# design.net
KiCad netlist of a schematic drawn in Altium Designer
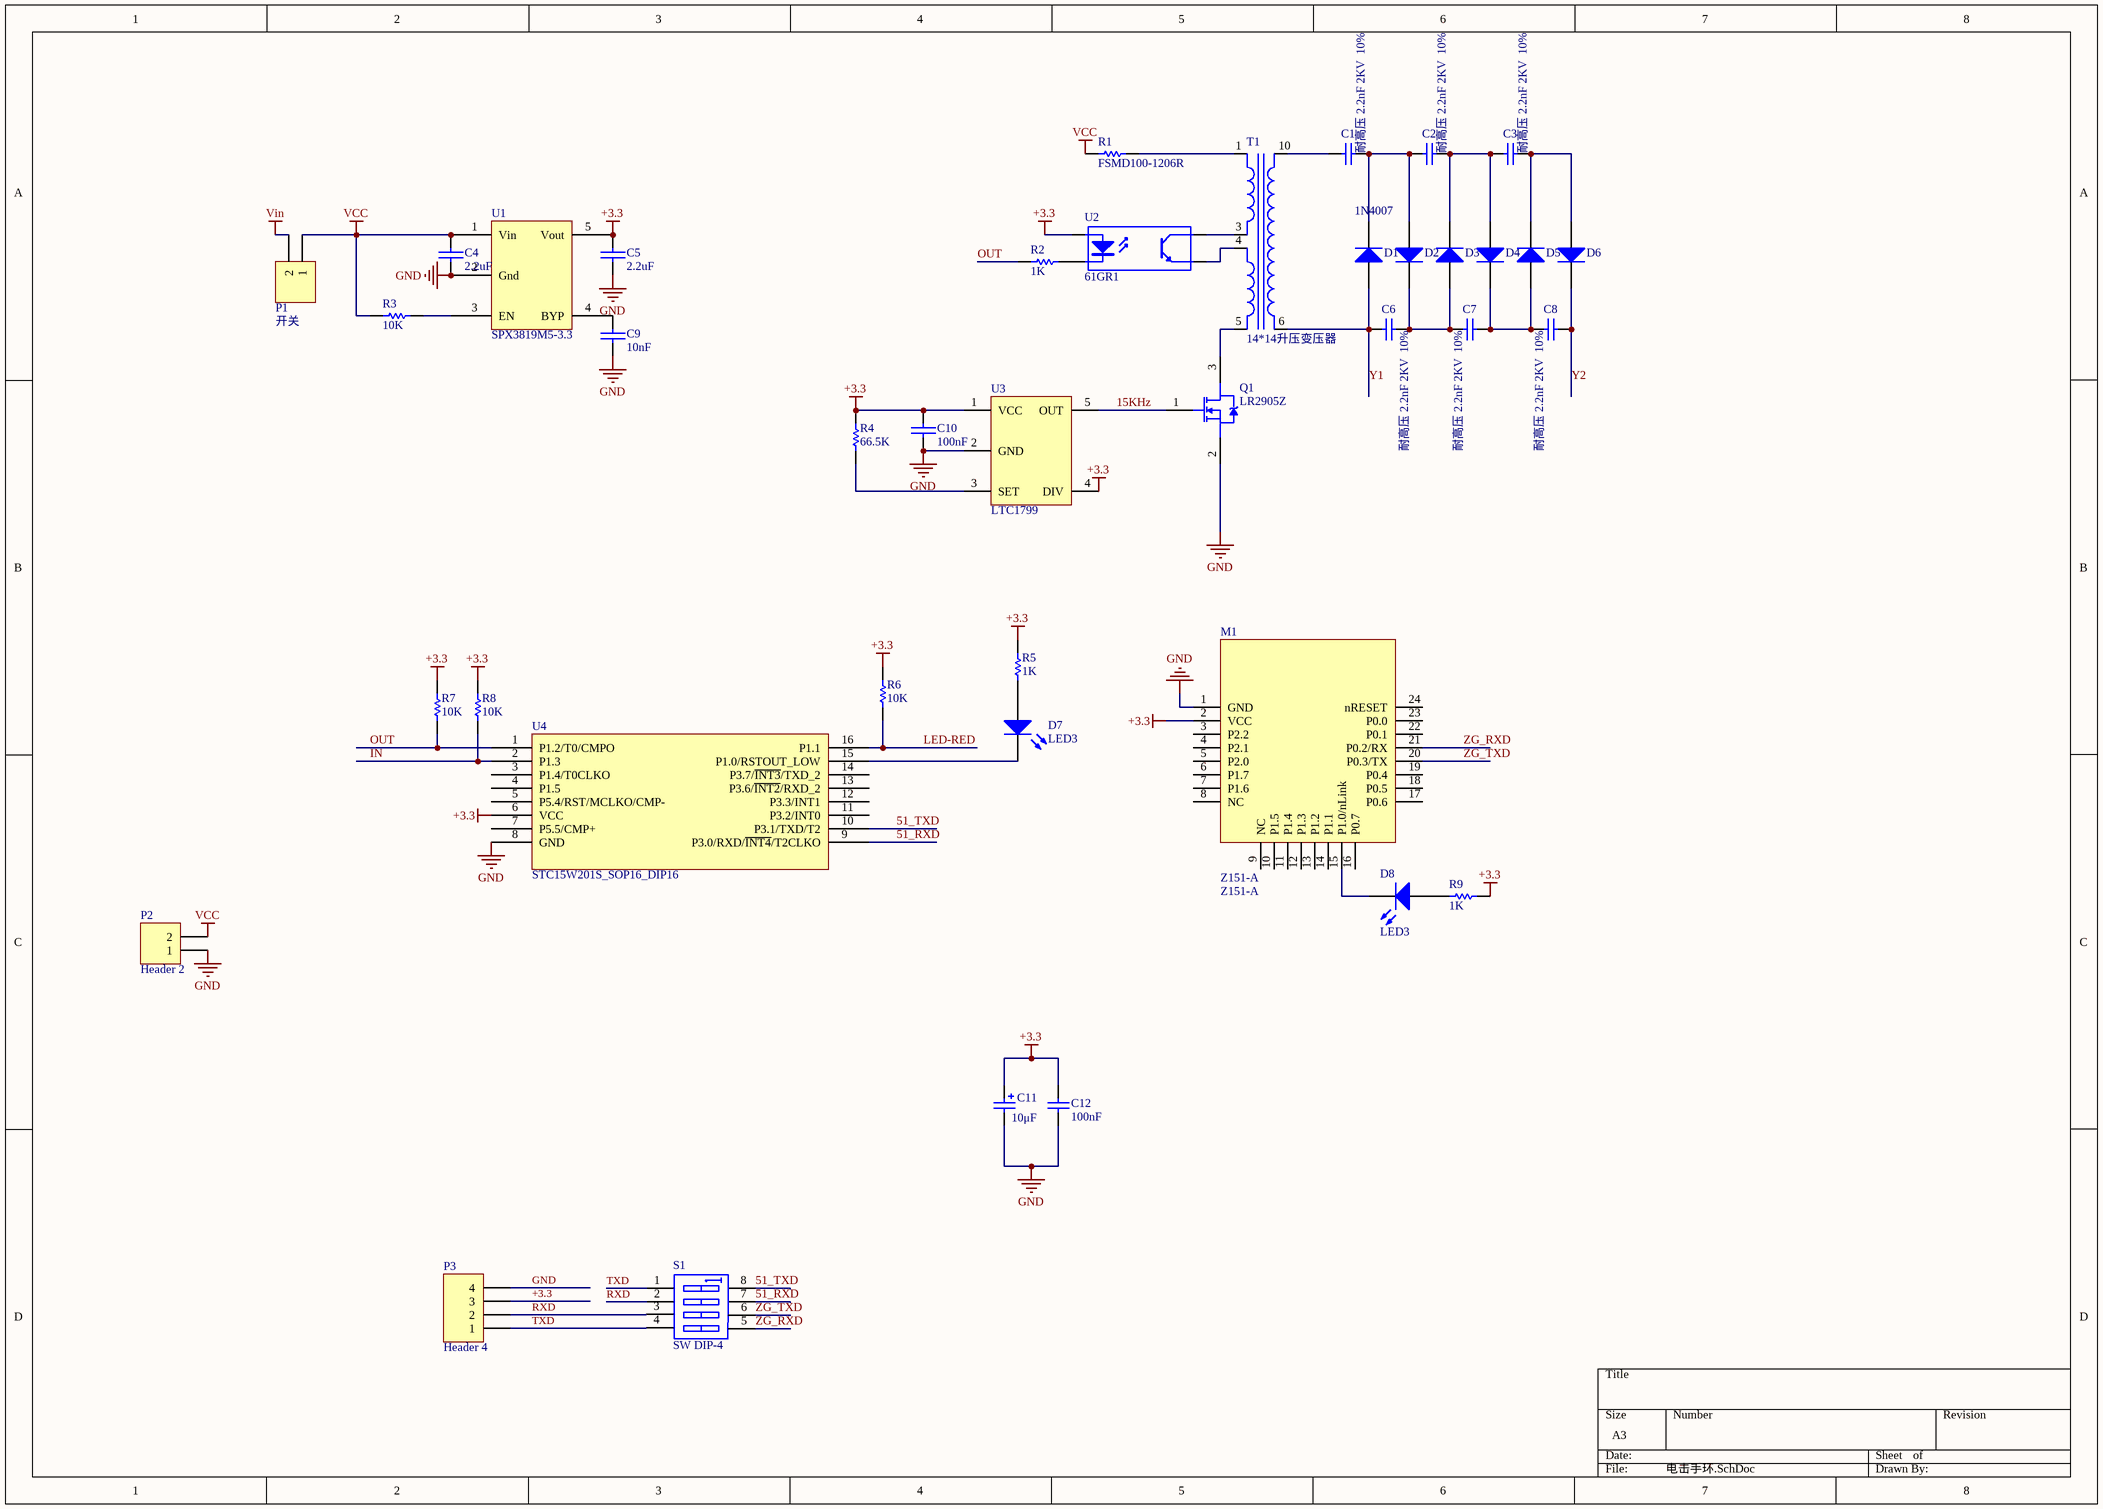
[diagram p0: 电击手环.SchDoc]

(export (version "E")
  (design (tool "Eeschema 10.0.6"))
  (components
    (comp (ref "C1")
      (value "耐高压 2.2nF 2KV  10%")
      (footprint "1206")
      (description "Capacitor")
      (fields (field (name "PUBLISHER") "Altium Limited"))
      (libsource (lib "AA-SCH") (part "Cap"))
    )
    (comp (ref "C2")
      (value "耐高压 2.2nF 2KV  10%")
      (footprint "1206")
      (description "Capacitor")
      (fields (field (name "PUBLISHER") "Altium Limited"))
      (libsource (lib "AA-SCH") (part "Cap"))
    )
    (comp (ref "C3")
      (value "耐高压 2.2nF 2KV  10%")
      (footprint "1206")
      (description "Capacitor")
      (fields (field (name "PUBLISHER") "Altium Limited"))
      (libsource (lib "AA-SCH") (part "Cap"))
    )
    (comp (ref "C4")
      (value "2.2uF")
      (footprint "0603")
      (description "Capacitor")
      (libsource (lib "*") (part "CAP"))
    )
    (comp (ref "C5")
      (value "2.2uF")
      (footprint "0603")
      (description "Capacitor")
      (libsource (lib "*") (part "CAP"))
    )
    (comp (ref "C6")
      (value "耐高压 2.2nF 2KV  10%")
      (footprint "1206")
      (description "Capacitor")
      (fields (field (name "PUBLISHER") "Altium Limited"))
      (libsource (lib "AA-SCH") (part "Cap"))
    )
    (comp (ref "C7")
      (value "耐高压 2.2nF 2KV  10%")
      (footprint "1206")
      (description "Capacitor")
      (fields (field (name "PUBLISHER") "Altium Limited"))
      (libsource (lib "AA-SCH") (part "Cap"))
    )
    (comp (ref "C8")
      (value "耐高压 2.2nF 2KV  10%")
      (footprint "1206")
      (description "Capacitor")
      (fields (field (name "PUBLISHER") "Altium Limited"))
      (libsource (lib "AA-SCH") (part "Cap"))
    )
    (comp (ref "C9")
      (value "10nF")
      (footprint "0603")
      (description "Capacitor")
      (libsource (lib "*") (part "CAP"))
    )
    (comp (ref "C10")
      (value "100nF")
      (footprint "R0603(1608)")
      (description "Capacitor")
      (libsource (lib "") (part "CAP_1"))
    )
    (comp (ref "C11")
      (value "10μF")
      (footprint "0603")
      (description "Polarized Capacitor (Radial)")
      (fields
        (field (name "MANUFACTURER") "Generic Components")
        (field (name "PUBLISHER") "Altium Hobart Technology Centre")
      )
      (libsource (lib "Miscellaneous Devices") (part "Cap Pol1"))
    )
    (comp (ref "C12")
      (value "100nF")
      (footprint "0603")
      (description "Capacitor")
      (fields (field (name "PUBLISHER") "Altium Limited"))
      (libsource (lib "Miscellaneous Devices") (part "Cap"))
    )
    (comp (ref "D1")
      (value "1N4007")
      (footprint "DO-214AA")
      (description "二极管")
      (fields (field (name "PUBLISHER") "Altium Limited"))
      (libsource (lib "AA-SCH") (part "Diode_1"))
    )
    (comp (ref "D2")
      (value "1N4007")
      (footprint "DO-214AA")
      (description "二极管")
      (fields (field (name "PUBLISHER") "Altium Limited"))
      (libsource (lib "AA-SCH") (part "Diode_1"))
    )
    (comp (ref "D3")
      (value "1N4007")
      (footprint "DO-214AA")
      (description "二极管")
      (fields (field (name "PUBLISHER") "Altium Limited"))
      (libsource (lib "AA-SCH") (part "Diode_1"))
    )
    (comp (ref "D4")
      (value "1N4007")
      (footprint "DO-214AA")
      (description "二极管")
      (fields (field (name "PUBLISHER") "Altium Limited"))
      (libsource (lib "AA-SCH") (part "Diode_1"))
    )
    (comp (ref "D5")
      (value "1N4007")
      (footprint "DO-214AA")
      (description "二极管")
      (fields (field (name "PUBLISHER") "Altium Limited"))
      (libsource (lib "AA-SCH") (part "Diode_1"))
    )
    (comp (ref "D6")
      (value "1N4007")
      (footprint "DO-214AA")
      (description "二极管")
      (fields (field (name "PUBLISHER") "Altium Limited"))
      (libsource (lib "AA-SCH") (part "Diode_1"))
    )
    (comp (ref "D7")
      (value "LED3")
      (footprint "LED0805")
      (description "Typical BLUE SiC LED")
      (fields (field (name "PUBLISHER") "Altium Limited"))
      (libsource (lib "Miscellaneous Devices") (part "LED3"))
    )
    (comp (ref "D8")
      (value "LED3")
      (footprint "LED0805")
      (description "Typical BLUE SiC LED")
      (fields (field (name "PUBLISHER") "Altium Limited"))
      (libsource (lib "Miscellaneous Devices") (part "LED3"))
    )
    (comp (ref "M1")
      (value "Z151-A")
      (footprint "Z151-A")
      (description "Z151板载天线版本：Z151-A")
      (fields (field (name "MANUFACTURER") "Ghostyu") (field (name "PART VALUE") "Z151-A"))
      (libsource (lib "AA-SCH") (part "Z151-A"))
    )
    (comp (ref "P1")
      (value "开关")
      (footprint "HDR1X2")
      (description "Header, 2-Pin")
      (fields (field (name "PUBLISHER") "Altium Limited"))
      (libsource (lib "") (part "Header 2_1"))
    )
    (comp (ref "P2")
      (value "Header 2")
      (footprint "HDR1X2")
      (description "Header, 2-Pin")
      (fields (field (name "PUBLISHER") "Altium Limited"))
      (libsource (lib "Miscellaneous Connectors") (part "Header 2"))
    )
    (comp (ref "P3")
      (value "Header 4")
      (footprint "HDR1X4")
      (description "Header, 4-Pin")
      (fields (field (name "PUBLISHER") "Altium Limited"))
      (libsource (lib "Miscellaneous Connectors") (part "Header 4"))
    )
    (comp (ref "Q1")
      (value "LR2905Z")
      (footprint "TO-252AA_N")
      (description "N-Channel MOSFET")
      (fields (field (name "PUBLISHER") "Altium Limited"))
      (libsource (lib "AA-SCH") (part "MOSFET-N"))
    )
    (comp (ref "R1")
      (value "FSMD100-1206R")
      (footprint "1206")
      (description "Resistor")
      (fields (field (name "PUBLISHER") "Altium Limited"))
      (libsource (lib "Miscellaneous Devices") (part "Res1"))
    )
    (comp (ref "R2")
      (value "1K")
      (footprint "R0805(2012)")
      (description "Resistor")
      (fields (field (name "PUBLISHER") "Altium Limited"))
      (libsource (lib "Miscellaneous Devices") (part "Res1"))
    )
    (comp (ref "R3")
      (value "10K")
      (footprint "0603")
      (description "Resistor")
      (fields (field (name "PUBLISHER") "Altium Limited"))
      (libsource (lib "Miscellaneous Devices") (part "Res1"))
    )
    (comp (ref "R4")
      (value "66.5K")
      (footprint "R0603(1608)")
      (description "Resistor")
      (fields (field (name "PUBLISHER") "Altium Limited"))
      (libsource (lib "Miscellaneous Devices") (part "Res1"))
    )
    (comp (ref "R5")
      (value "1K")
      (footprint "0603")
      (description "Resistor")
      (fields (field (name "PUBLISHER") "Altium Limited"))
      (libsource (lib "Miscellaneous Devices") (part "Res1"))
    )
    (comp (ref "R6")
      (value "10K")
      (footprint "0603")
      (description "Resistor")
      (fields (field (name "PUBLISHER") "Altium Limited"))
      (libsource (lib "Miscellaneous Devices") (part "Res1"))
    )
    (comp (ref "R7")
      (value "10K")
      (footprint "0603")
      (description "Resistor")
      (fields (field (name "PUBLISHER") "Altium Limited"))
      (libsource (lib "Miscellaneous Devices") (part "Res1"))
    )
    (comp (ref "R8")
      (value "10K")
      (footprint "0603")
      (description "Resistor")
      (fields (field (name "PUBLISHER") "Altium Limited"))
      (libsource (lib "Miscellaneous Devices") (part "Res1"))
    )
    (comp (ref "R9")
      (value "1K")
      (footprint "0603")
      (description "Resistor")
      (fields (field (name "PUBLISHER") "Altium Limited"))
      (libsource (lib "Miscellaneous Devices") (part "Res1"))
    )
    (comp (ref "S1")
      (value "SW DIP-4")
      (footprint "拨码开关1.27-5.4-4P")
      (description "DIP Switch, 2 Position, SPST")
      (fields (field (name "PUBLISHER") "Altium Limited"))
      (libsource (lib "yuanjian ") (part "SW DIP-4"))
    )
    (comp (ref "T1")
      (value "14*14升压变压器")
      (footprint "14*14 升压变压器")
      (libsource (lib "AA-SCH") (part "14*14升压变压器"))
    )
    (comp (ref "U1")
      (value "SPX3819M5-3.3")
      (footprint "AA-PCB :SOT-25")
      (description "Low Noise, 300mA and 500mA CMOS LDO Regulators")
      (libsource (lib "AA-SCH") (part "SP6205"))
    )
    (comp (ref "U2")
      (value "61GR1")
      (footprint "G3VM")
      (description "4-Pin Phototransistor Optocoupler")
      (fields (field (name "PUBLISHER") "Altium Limited"))
      (libsource (lib "Miscellaneous Devices") (part "Optoisolator1"))
    )
    (comp (ref "U3") (value "LTC1799") (footprint "SOT-25B") (libsource (lib "AA-SCH") (part "LTC1799")))
    (comp (ref "U4")
      (value "STC15W201S_SOP16_DIP16")
      (footprint "SO-16")
      (libsource (lib "AA-SCH") (part "STC15W201S_SOP16_DIP16"))
    )
  )
  (nets
    (net (code "1") (name "+3.3") (class "Default")
      (node (ref "C10") (pin "1") (pinfunction "1_1") (pintype "passive"))
      (node (ref "C11") (pin "1") (pinfunction "1_1") (pintype "passive"))
      (node (ref "C12") (pin "2") (pinfunction "2_2") (pintype "passive"))
      (node (ref "C5") (pin "1") (pinfunction "1_1") (pintype "passive"))
      (node (ref "M1") (pin "2") (pinfunction "VCC_2") (pintype "passive"))
      (node (ref "P3") (pin "3") (pinfunction "3_3") (pintype "passive"))
      (node (ref "R4") (pin "1") (pinfunction "1_1") (pintype "passive"))
      (node (ref "R5") (pin "1") (pinfunction "1_1") (pintype "passive"))
      (node (ref "R6") (pin "2") (pinfunction "2_2") (pintype "passive"))
      (node (ref "R7") (pin "2") (pinfunction "2_2") (pintype "passive"))
      (node (ref "R8") (pin "2") (pinfunction "2_2") (pintype "passive"))
      (node (ref "R9") (pin "1") (pinfunction "1_1") (pintype "passive"))
      (node (ref "U1") (pin "5") (pinfunction "Vout_5") (pintype "power_in"))
      (node (ref "U2") (pin "1") (pinfunction "A_1") (pintype "passive"))
      (node (ref "U3") (pin "1") (pinfunction "VCC_1") (pintype "passive"))
      (node (ref "U3") (pin "4") (pinfunction "DIV_4") (pintype "passive"))
      (node (ref "U4") (pin "6") (pinfunction "VCC_6") (pintype "passive"))
    )
    (net (code "2") (name "/15KHz") (class "Default")
      (node (ref "Q1") (pin "1") (pinfunction "G1_1") (pintype "power_in"))
      (node (ref "U3") (pin "5") (pinfunction "OUT_5") (pintype "passive"))
    )
    (net (code "3") (name "/51_RXD") (class "Default")
      (node (ref "S1") (pin "7") (pinfunction "7_7") (pintype "passive"))
      (node (ref "U4") (pin "9") (pinfunction "P3.0/RXD/~{INT4}/T2CLKO_9") (pintype "passive"))
    )
    (net (code "4") (name "/51_TXD") (class "Default")
      (node (ref "S1") (pin "8") (pinfunction "8_8") (pintype "passive"))
      (node (ref "U4") (pin "10") (pinfunction "P3.1/TXD/T2_10") (pintype "passive"))
    )
    (net (code "5") (name "/IN") (class "Default")
      (node (ref "R8") (pin "1") (pinfunction "1_1") (pintype "passive"))
      (node (ref "U4") (pin "2") (pinfunction "P1.3_2") (pintype "passive"))
    )
    (net (code "6") (name "/LED-RED") (class "Default")
      (node (ref "R6") (pin "1") (pinfunction "1_1") (pintype "passive"))
      (node (ref "U4") (pin "16") (pinfunction "P1.1_16") (pintype "passive"))
    )
    (net (code "7") (name "/OUT") (class "Default")
      (node (ref "R2") (pin "2") (pinfunction "2_2") (pintype "passive"))
      (node (ref "R7") (pin "1") (pinfunction "1_1") (pintype "passive"))
      (node (ref "U4") (pin "1") (pinfunction "P1.2/T0/CMPO_1") (pintype "passive"))
    )
    (net (code "8") (name "/RXD") (class "Default")
      (node (ref "P3") (pin "2") (pinfunction "2_2") (pintype "passive"))
      (node (ref "S1") (pin "2") (pinfunction "2_2") (pintype "passive"))
      (node (ref "S1") (pin "3") (pinfunction "3_3") (pintype "passive"))
    )
    (net (code "9") (name "/TXD") (class "Default")
      (node (ref "P3") (pin "1") (pinfunction "1_1") (pintype "passive"))
      (node (ref "S1") (pin "1") (pinfunction "1_1") (pintype "passive"))
      (node (ref "S1") (pin "4") (pinfunction "4_4") (pintype "passive"))
    )
    (net (code "10") (name "/Y1") (class "Default")
      (node (ref "C6") (pin "2") (pinfunction "2_2") (pintype "passive"))
      (node (ref "D1") (pin "1") (pinfunction "A_1") (pintype "passive"))
      (node (ref "T1") (pin "6") (pinfunction "Pri+_6") (pintype "passive"))
    )
    (net (code "11") (name "/Y2") (class "Default")
      (node (ref "C8") (pin "1") (pinfunction "1_1") (pintype "passive"))
      (node (ref "D6") (pin "2") (pinfunction "K_2") (pintype "passive"))
    )
    (net (code "12") (name "/ZG_RXD") (class "Default")
      (node (ref "M1") (pin "21") (pinfunction "P0.2/RX_21") (pintype "passive"))
      (node (ref "S1") (pin "5") (pinfunction "5_5") (pintype "passive"))
    )
    (net (code "13") (name "/ZG_TXD") (class "Default")
      (node (ref "M1") (pin "20") (pinfunction "P0.3/TX_20") (pintype "passive"))
      (node (ref "S1") (pin "6") (pinfunction "6_6") (pintype "passive"))
    )
    (net (code "14") (name "GND") (class "Default")
      (node (ref "C10") (pin "2") (pinfunction "2_2") (pintype "passive"))
      (node (ref "C11") (pin "2") (pinfunction "2_2") (pintype "passive"))
      (node (ref "C12") (pin "1") (pinfunction "1_1") (pintype "passive"))
      (node (ref "C4") (pin "2") (pinfunction "2_2") (pintype "passive"))
      (node (ref "C5") (pin "2") (pinfunction "2_2") (pintype "passive"))
      (node (ref "C9") (pin "2") (pinfunction "2_2") (pintype "passive"))
      (node (ref "M1") (pin "1") (pinfunction "GND_1") (pintype "passive"))
      (node (ref "P2") (pin "1") (pinfunction "1_1") (pintype "passive"))
      (node (ref "P3") (pin "4") (pinfunction "4_4") (pintype "passive"))
      (node (ref "Q1") (pin "2") (pinfunction "S1_2") (pintype "power_in"))
      (node (ref "U1") (pin "2") (pinfunction "Gnd_2") (pintype "power_in"))
      (node (ref "U3") (pin "2") (pinfunction "GND_2") (pintype "passive"))
      (node (ref "U4") (pin "8") (pinfunction "GND_8") (pintype "passive"))
    )
    (net (code "15") (name "Net-(D1-K)") (class "Default")
      (node (ref "C1") (pin "1") (pinfunction "1_1") (pintype "passive"))
      (node (ref "C2") (pin "2") (pinfunction "2_2") (pintype "passive"))
      (node (ref "D1") (pin "2") (pinfunction "K_2") (pintype "passive"))
      (node (ref "D2") (pin "1") (pinfunction "A_1") (pintype "passive"))
    )
    (net (code "16") (name "Net-(D2-K)") (class "Default")
      (node (ref "C6") (pin "1") (pinfunction "1_1") (pintype "passive"))
      (node (ref "C7") (pin "2") (pinfunction "2_2") (pintype "passive"))
      (node (ref "D2") (pin "2") (pinfunction "K_2") (pintype "passive"))
      (node (ref "D3") (pin "1") (pinfunction "A_1") (pintype "passive"))
    )
    (net (code "17") (name "Net-(D3-K)") (class "Default")
      (node (ref "C2") (pin "1") (pinfunction "1_1") (pintype "passive"))
      (node (ref "C3") (pin "2") (pinfunction "2_2") (pintype "passive"))
      (node (ref "D3") (pin "2") (pinfunction "K_2") (pintype "passive"))
      (node (ref "D4") (pin "1") (pinfunction "A_1") (pintype "passive"))
    )
    (net (code "18") (name "Net-(D4-K)") (class "Default")
      (node (ref "C7") (pin "1") (pinfunction "1_1") (pintype "passive"))
      (node (ref "C8") (pin "2") (pinfunction "2_2") (pintype "passive"))
      (node (ref "D4") (pin "2") (pinfunction "K_2") (pintype "passive"))
      (node (ref "D5") (pin "1") (pinfunction "A_1") (pintype "passive"))
    )
    (net (code "19") (name "Net-(D5-K)") (class "Default")
      (node (ref "C3") (pin "1") (pinfunction "1_1") (pintype "passive"))
      (node (ref "D5") (pin "2") (pinfunction "K_2") (pintype "passive"))
      (node (ref "D6") (pin "1") (pinfunction "A_1") (pintype "passive"))
    )
    (net (code "20") (name "Net-(D7-A)") (class "Default")
      (node (ref "D7") (pin "1") (pinfunction "A_1") (pintype "passive"))
      (node (ref "R5") (pin "2") (pinfunction "2_2") (pintype "passive"))
    )
    (net (code "21") (name "Net-(D7-K)") (class "Default")
      (node (ref "D7") (pin "2") (pinfunction "K_2") (pintype "passive"))
      (node (ref "U4") (pin "15") (pinfunction "P1.0/RSTOUT_LOW_15") (pintype "passive"))
    )
    (net (code "22") (name "Net-(D8-A)") (class "Default")
      (node (ref "D8") (pin "1") (pinfunction "A_1") (pintype "passive"))
      (node (ref "R9") (pin "2") (pinfunction "2_2") (pintype "passive"))
    )
    (net (code "23") (name "Net-(D8-K)") (class "Default")
      (node (ref "D8") (pin "2") (pinfunction "K_2") (pintype "passive"))
      (node (ref "M1") (pin "15") (pinfunction "P1.0/nLink_15") (pintype "passive"))
    )
    (net (code "24") (name "Net-(Q1-D1)") (class "Default")
      (node (ref "Q1") (pin "3") (pinfunction "D1_3") (pintype "power_in"))
      (node (ref "T1") (pin "5") (pinfunction "Sec1+_5") (pintype "passive"))
    )
    (net (code "25") (name "Net-(T1-Pri-)") (class "Default")
      (node (ref "C1") (pin "2") (pinfunction "2_2") (pintype "passive"))
      (node (ref "T1") (pin "10") (pinfunction "Pri-_10") (pintype "passive"))
    )
    (net (code "26") (name "Net-(T1-Sec1-)") (class "Default")
      (node (ref "T1") (pin "4") (pinfunction "Sec1-_4") (pintype "passive"))
      (node (ref "U2") (pin "3") (pinfunction "E_3") (pintype "passive"))
    )
    (net (code "27") (name "Net-(T1-Sec2+)") (class "Default")
      (node (ref "T1") (pin "3") (pinfunction "Sec2+_3") (pintype "passive"))
      (node (ref "U2") (pin "4") (pinfunction "C_4") (pintype "passive"))
    )
    (net (code "28") (name "Net-(T1-Sec2-)") (class "Default")
      (node (ref "R1") (pin "2") (pinfunction "2_2") (pintype "passive"))
      (node (ref "T1") (pin "1") (pinfunction "Sec2-_1") (pintype "passive"))
    )
    (net (code "29") (name "Net-(U1-BYP)") (class "Default")
      (node (ref "C9") (pin "1") (pinfunction "1_1") (pintype "passive"))
      (node (ref "U1") (pin "4") (pinfunction "BYP_4") (pintype "power_in"))
    )
    (net (code "30") (name "Net-(U1-EN)") (class "Default")
      (node (ref "R3") (pin "1") (pinfunction "1_1") (pintype "passive"))
      (node (ref "U1") (pin "3") (pinfunction "EN_3") (pintype "power_in"))
    )
    (net (code "31") (name "Net-(U2-K)") (class "Default")
      (node (ref "R2") (pin "1") (pinfunction "1_1") (pintype "passive"))
      (node (ref "U2") (pin "2") (pinfunction "K_2") (pintype "passive"))
    )
    (net (code "32") (name "Net-(U3-SET)") (class "Default")
      (node (ref "R4") (pin "2") (pinfunction "2_2") (pintype "passive"))
      (node (ref "U3") (pin "3") (pinfunction "SET_3") (pintype "passive"))
    )
    (net (code "33") (name "VCC") (class "Default")
      (node (ref "C4") (pin "1") (pinfunction "1_1") (pintype "passive"))
      (node (ref "P1") (pin "1") (pinfunction "1_1") (pintype "passive"))
      (node (ref "P2") (pin "2") (pinfunction "2_2") (pintype "passive"))
      (node (ref "R1") (pin "1") (pinfunction "1_1") (pintype "passive"))
      (node (ref "R3") (pin "2") (pinfunction "2_2") (pintype "passive"))
      (node (ref "U1") (pin "1") (pinfunction "Vin_1") (pintype "power_in"))
    )
    (net (code "34") (name "Vin") (class "Default")
      (node (ref "P1") (pin "2") (pinfunction "2_2") (pintype "passive"))
    )
    (net (code "35") (name "unconnected-(M1-NC-Pad8)") (class "Default")
      (node (ref "M1") (pin "8") (pinfunction "NC_8") (pintype "passive"))
    )
    (net (code "36") (name "unconnected-(M1-NC-Pad9)") (class "Default")
      (node (ref "M1") (pin "9") (pinfunction "NC_9") (pintype "passive"))
    )
    (net (code "37") (name "unconnected-(M1-P0.0-Pad23)") (class "Default")
      (node (ref "M1") (pin "23") (pinfunction "P0.0_23") (pintype "passive"))
    )
    (net (code "38") (name "unconnected-(M1-P0.1-Pad22)") (class "Default")
      (node (ref "M1") (pin "22") (pinfunction "P0.1_22") (pintype "passive"))
    )
    (net (code "39") (name "unconnected-(M1-P0.4-Pad19)") (class "Default")
      (node (ref "M1") (pin "19") (pinfunction "P0.4_19") (pintype "passive"))
    )
    (net (code "40") (name "unconnected-(M1-P0.5-Pad18)") (class "Default")
      (node (ref "M1") (pin "18") (pinfunction "P0.5_18") (pintype "passive"))
    )
    (net (code "41") (name "unconnected-(M1-P0.6-Pad17)") (class "Default")
      (node (ref "M1") (pin "17") (pinfunction "P0.6_17") (pintype "passive"))
    )
    (net (code "42") (name "unconnected-(M1-P0.7-Pad16)") (class "Default")
      (node (ref "M1") (pin "16") (pinfunction "P0.7_16") (pintype "passive"))
    )
    (net (code "43") (name "unconnected-(M1-P1.1-Pad14)") (class "Default")
      (node (ref "M1") (pin "14") (pinfunction "P1.1_14") (pintype "passive"))
    )
    (net (code "44") (name "unconnected-(M1-P1.2-Pad13)") (class "Default")
      (node (ref "M1") (pin "13") (pinfunction "P1.2_13") (pintype "passive"))
    )
    (net (code "45") (name "unconnected-(M1-P1.3-Pad12)") (class "Default")
      (node (ref "M1") (pin "12") (pinfunction "P1.3_12") (pintype "passive"))
    )
    (net (code "46") (name "unconnected-(M1-P1.4-Pad11)") (class "Default")
      (node (ref "M1") (pin "11") (pinfunction "P1.4_11") (pintype "passive"))
    )
    (net (code "47") (name "unconnected-(M1-P1.5-Pad10)") (class "Default")
      (node (ref "M1") (pin "10") (pinfunction "P1.5_10") (pintype "passive"))
    )
    (net (code "48") (name "unconnected-(M1-P1.6-Pad7)") (class "Default")
      (node (ref "M1") (pin "7") (pinfunction "P1.6_7") (pintype "passive"))
    )
    (net (code "49") (name "unconnected-(M1-P1.7-Pad6)") (class "Default")
      (node (ref "M1") (pin "6") (pinfunction "P1.7_6") (pintype "passive"))
    )
    (net (code "50") (name "unconnected-(M1-P2.0-Pad5)") (class "Default")
      (node (ref "M1") (pin "5") (pinfunction "P2.0_5") (pintype "passive"))
    )
    (net (code "51") (name "unconnected-(M1-P2.1-Pad4)") (class "Default")
      (node (ref "M1") (pin "4") (pinfunction "P2.1_4") (pintype "passive"))
    )
    (net (code "52") (name "unconnected-(M1-P2.2-Pad3)") (class "Default")
      (node (ref "M1") (pin "3") (pinfunction "P2.2_3") (pintype "passive"))
    )
    (net (code "53") (name "unconnected-(M1-nRESET-Pad24)") (class "Default")
      (node (ref "M1") (pin "24") (pinfunction "nRESET_24") (pintype "passive"))
    )
    (net (code "54") (name "unconnected-(U4-P1.4{slash}T0CLKO-Pad3)") (class "Default")
      (node (ref "U4") (pin "3") (pinfunction "P1.4/T0CLKO_3") (pintype "passive"))
    )
    (net (code "55") (name "unconnected-(U4-P1.5-Pad4)") (class "Default")
      (node (ref "U4") (pin "4") (pinfunction "P1.5_4") (pintype "passive"))
    )
    (net (code "56") (name "unconnected-(U4-P3.2{slash}INT0-Pad11)") (class "Default")
      (node (ref "U4") (pin "11") (pinfunction "P3.2/INT0_11") (pintype "passive"))
    )
    (net (code "57") (name "unconnected-(U4-P3.3{slash}INT1-Pad12)") (class "Default")
      (node (ref "U4") (pin "12") (pinfunction "P3.3/INT1_12") (pintype "passive"))
    )
    (net (code "58") (name "unconnected-(U4-P3.6{slash}~{INT2}{slash}RXD_2-Pad13)") (class "Default")
      (node (ref "U4") (pin "13") (pinfunction "P3.6/~{INT2}/RXD_2_13") (pintype "passive"))
    )
    (net (code "59") (name "unconnected-(U4-P3.7{slash}~{INT3}{slash}TXD_2-Pad14)") (class "Default")
      (node (ref "U4") (pin "14") (pinfunction "P3.7/~{INT3}/TXD_2_14") (pintype "passive"))
    )
    (net (code "60") (name "unconnected-(U4-P5.4{slash}RST{slash}MCLKO{slash}CMP--Pad5)") (class "Default")
      (node (ref "U4") (pin "5") (pinfunction "P5.4/RST/MCLKO/CMP-_5") (pintype "passive"))
    )
    (net (code "61") (name "unconnected-(U4-P5.5{slash}CMP+-Pad7)") (class "Default")
      (node (ref "U4") (pin "7") (pinfunction "P5.5/CMP+_7") (pintype "passive"))
    )
  )
)
